# Sheet1.net
KiCad netlist of a schematic drawn in Altium Designer
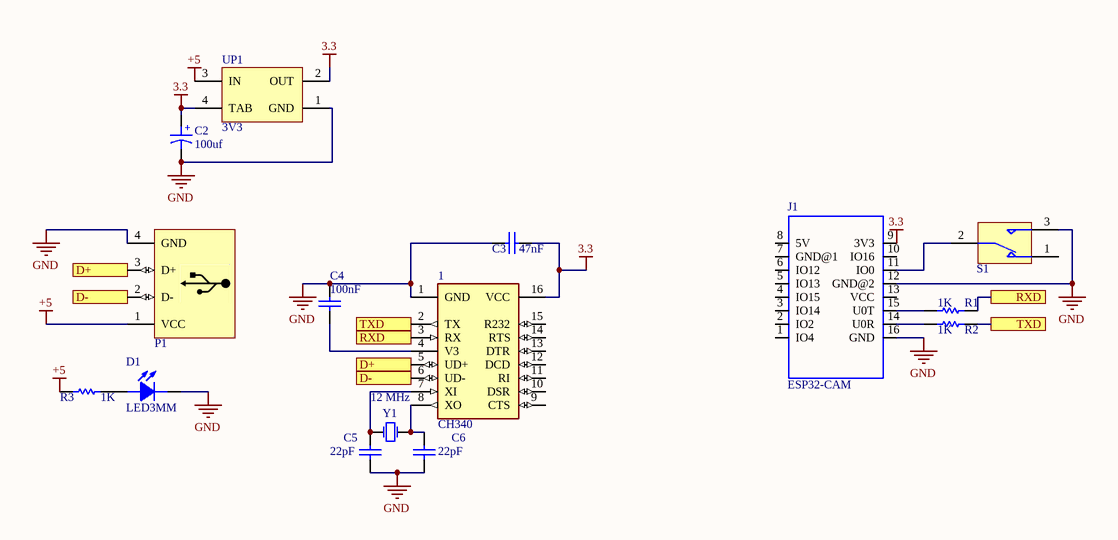
[diagram p0: Sheet1.SchDoc]

(export (version "E")
  (design (tool "Eeschema 10.0.6"))
  (components
    (comp (ref "1")
      (value "CH340")
      (footprint "SOIC16")
      (description "Circuit Breaker Magnetic 3Pole 40A 240VAC")
      (fields (field (name "MF") "Eaton"))
      (libsource (lib "CH340") (part "CH340"))
    )
    (comp (ref "C2")
      (value "100uf")
      (footprint "Cap electrolitic radial 6.3x12-2.5")
      (description "Cap electrolitic radial")
      (fields (field (name "DESIGNER") "Abbas Basereh"))
      (libsource (lib "Altium") (part "Cap ELECTROLITIC TOTAL SIZE"))
    )
    (comp (ref "C3")
      (value "47nF")
      (footprint "Cap-100nF")
      (description "CAP Ceramic Total")
      (fields (field (name "DESIGNER") "Ali Hafizi"))
      (libsource (lib "Altium") (part "CAP CERAMIC TOTAL SIZE"))
    )
    (comp (ref "C4")
      (value "100nF")
      (footprint "Cap-100nF")
      (description "CAP Ceramic Total")
      (fields (field (name "DESIGNER") "Ali Hafizi"))
      (libsource (lib "Altium") (part "CAP CERAMIC TOTAL SIZE"))
    )
    (comp (ref "C5")
      (value "22pF")
      (footprint "Cap-100nF")
      (description "CAP Ceramic Total")
      (fields (field (name "DESIGNER") "Ali Hafizi"))
      (libsource (lib "Altium") (part "CAP CERAMIC TOTAL SIZE"))
    )
    (comp (ref "C6")
      (value "22pF")
      (footprint "Cap-100nF")
      (description "CAP Ceramic Total")
      (fields (field (name "DESIGNER") "Ali Hafizi"))
      (libsource (lib "Altium") (part "CAP CERAMIC TOTAL SIZE"))
    )
    (comp (ref "D1")
      (value "LED3MM")
      (footprint "LED3mm_GRN")
      (description "Light Emitting Diode")
      (fields (field (name "DESIGNER") "Ali Hafizi"))
      (libsource (lib "Altium") (part "LED 3MM"))
    )
    (comp (ref "J1")
      (value "ESP32-CAM")
      (footprint "ESP32-CAM")
      (description "The smallest 802.11b/g/n Wi-Fi BT SoC Module")
      (fields (field (name "MF") "AI-Thinker"))
      (libsource (lib "ESP32-CAM") (part "ESP32-CAM"))
    )
    (comp (ref "P1")
      (value "USB Connector")
      (footprint "USB A TYPE Right Angle")
      (description "USB Connector-A Type")
      (libsource (lib "Altium") (part "USB A-Type"))
    )
    (comp (ref "R1")
      (value "1K")
      (footprint "RES-(1/4)")
      (description "TOTAL DIP RESISTOR PACK")
      (fields (field (name "DESIGNER") "Ali Hafizi"))
      (libsource (lib "Altium") (part "RES DIP PACKAGE"))
    )
    (comp (ref "R2")
      (value "1K")
      (footprint "RES-(1/4)")
      (description "TOTAL DIP RESISTOR PACK")
      (fields (field (name "DESIGNER") "Ali Hafizi"))
      (libsource (lib "Altium") (part "RES DIP PACKAGE"))
    )
    (comp (ref "R3")
      (value "1K")
      (footprint "RES-(1/4)")
      (description "TOTAL DIP RESISTOR PACK")
      (fields (field (name "DESIGNER") "Ali Hafizi"))
      (libsource (lib "Altium") (part "RES DIP PACKAGE"))
    )
    (comp (ref "S1")
      (value "Switch SPDT_Subminiator")
      (footprint "SPDT Subminiator")
      (description "Subminiator SPDT Switch")
      (libsource (lib "Altium") (part "Switch SPDT_Subminiator"))
    )
    (comp (ref "UP1")
      (value "3V3")
      (footprint "SOT223")
      (description "x.x Volt, 800mA Low-Dropout Linear Regulator, 4-pin SOT-223")
      (fields (field (name "DESIGNER") "Ali Hafizi"))
      (libsource (lib "Altium") (part "AMS1117-x.x"))
    )
    (comp (ref "Y1")
      (value "12 MHz")
      (footprint "XTAL 16MHZ")
      (description "XTAL Crystal")
      (fields (field (name "DESIGNER") "ABBAS BASEREH"))
      (libsource (lib "Altium") (part "XTAL"))
    )
  )
  (nets
    (net (code "1") (name "+5") (class "Default")
      (node (ref "P1") (pin "1") (pinfunction "VCC_1") (pintype "power_in"))
      (node (ref "R3") (pin "1") (pinfunction "1_1") (pintype "passive"))
      (node (ref "UP1") (pin "3") (pinfunction "IN_3") (pintype "power_in"))
    )
    (net (code "2") (name "/D+") (class "Default")
      (node (ref "1") (pin "5") (pinfunction "UD+_5") (pintype "bidirectional"))
      (node (ref "P1") (pin "3") (pinfunction "D+_3") (pintype "bidirectional"))
    )
    (net (code "3") (name "/D-") (class "Default")
      (node (ref "1") (pin "6") (pinfunction "UD-_6") (pintype "bidirectional"))
      (node (ref "P1") (pin "2") (pinfunction "D-_2") (pintype "bidirectional"))
    )
    (net (code "4") (name "/RXD") (class "Default")
      (node (ref "1") (pin "3") (pinfunction "RX_3") (pintype "input"))
      (node (ref "R1") (pin "1") (pinfunction "1_1") (pintype "passive"))
    )
    (net (code "5") (name "/TXD") (class "Default")
      (node (ref "1") (pin "2") (pinfunction "TX_2") (pintype "output"))
      (node (ref "R2") (pin "1") (pinfunction "1_1") (pintype "passive"))
    )
    (net (code "6") (name "3.3") (class "Default")
      (node (ref "1") (pin "16") (pinfunction "VCC_16") (pintype "power_in"))
      (node (ref "C2") (pin "1") (pinfunction "1_1") (pintype "passive"))
      (node (ref "C3") (pin "1") (pinfunction "1_1") (pintype "passive"))
      (node (ref "J1") (pin "9") (pinfunction "3V3_9") (pintype "power_in"))
      (node (ref "UP1") (pin "2") (pinfunction "OUT_2") (pintype "power_in"))
      (node (ref "UP1") (pin "4") (pinfunction "TAB_4") (pintype "power_in"))
    )
    (net (code "7") (name "GND") (class "Default")
      (node (ref "1") (pin "1") (pinfunction "GND_1") (pintype "power_in"))
      (node (ref "C2") (pin "2") (pinfunction "2_2") (pintype "passive"))
      (node (ref "C3") (pin "2") (pinfunction "2_2") (pintype "passive"))
      (node (ref "C4") (pin "2") (pinfunction "2_2") (pintype "passive"))
      (node (ref "C5") (pin "1") (pinfunction "1_1") (pintype "passive"))
      (node (ref "C6") (pin "1") (pinfunction "1_1") (pintype "passive"))
      (node (ref "D1") (pin "2") (pinfunction "CATHODE_2") (pintype "passive"))
      (node (ref "J1") (pin "12") (pinfunction "GND@2_12") (pintype "power_in"))
      (node (ref "J1") (pin "16") (pinfunction "GND_16") (pintype "power_in"))
      (node (ref "P1") (pin "4") (pinfunction "GND_4") (pintype "power_in"))
      (node (ref "S1") (pin "3") (pinfunction "3_3") (pintype "passive"))
      (node (ref "UP1") (pin "1") (pinfunction "GND_1") (pintype "power_in"))
    )
    (net (code "8") (name "Net-(1-V3)") (class "Default")
      (node (ref "1") (pin "4") (pinfunction "V3_4") (pintype "power_in"))
      (node (ref "C4") (pin "1") (pinfunction "1_1") (pintype "passive"))
    )
    (net (code "9") (name "Net-(1-XI)") (class "Default")
      (node (ref "1") (pin "7") (pinfunction "XI_7") (pintype "input"))
      (node (ref "C5") (pin "2") (pinfunction "2_2") (pintype "passive"))
      (node (ref "Y1") (pin "1") (pinfunction "OSC1_1") (pintype "passive"))
    )
    (net (code "10") (name "Net-(1-XO)") (class "Default")
      (node (ref "1") (pin "8") (pinfunction "XO_8") (pintype "output"))
      (node (ref "C6") (pin "2") (pinfunction "2_2") (pintype "passive"))
      (node (ref "Y1") (pin "2") (pinfunction "OSC2_2") (pintype "passive"))
    )
    (net (code "11") (name "Net-(D1-ANODE)") (class "Default")
      (node (ref "D1") (pin "1") (pinfunction "ANODE_1") (pintype "passive"))
      (node (ref "R3") (pin "2") (pinfunction "2_2") (pintype "passive"))
    )
    (net (code "12") (name "Net-(J1-IO0)") (class "Default")
      (node (ref "J1") (pin "11") (pinfunction "IO0_11") (pintype "bidirectional"))
      (node (ref "S1") (pin "2") (pinfunction "2_2") (pintype "passive"))
    )
    (net (code "13") (name "Net-(J1-U0R)") (class "Default")
      (node (ref "J1") (pin "14") (pinfunction "U0R_14") (pintype "power_in"))
      (node (ref "R2") (pin "2") (pinfunction "2_2") (pintype "passive"))
    )
    (net (code "14") (name "Net-(J1-U0T)") (class "Default")
      (node (ref "J1") (pin "15") (pinfunction "U0T_15") (pintype "bidirectional"))
      (node (ref "R1") (pin "2") (pinfunction "2_2") (pintype "passive"))
    )
    (net (code "15") (name "unconnected-(1-CTS-Pad9)") (class "Default")
      (node (ref "1") (pin "9") (pinfunction "CTS_9") (pintype "bidirectional"))
    )
    (net (code "16") (name "unconnected-(1-DCD-Pad12)") (class "Default")
      (node (ref "1") (pin "12") (pinfunction "DCD_12") (pintype "bidirectional"))
    )
    (net (code "17") (name "unconnected-(1-DSR-Pad10)") (class "Default")
      (node (ref "1") (pin "10") (pinfunction "DSR_10") (pintype "bidirectional"))
    )
    (net (code "18") (name "unconnected-(1-DTR-Pad13)") (class "Default")
      (node (ref "1") (pin "13") (pinfunction "DTR_13") (pintype "bidirectional"))
    )
    (net (code "19") (name "unconnected-(1-R232-Pad15)") (class "Default")
      (node (ref "1") (pin "15") (pinfunction "R232_15") (pintype "bidirectional"))
    )
    (net (code "20") (name "unconnected-(1-RI-Pad11)") (class "Default")
      (node (ref "1") (pin "11") (pinfunction "RI_11") (pintype "bidirectional"))
    )
    (net (code "21") (name "unconnected-(1-RTS-Pad14)") (class "Default")
      (node (ref "1") (pin "14") (pinfunction "RTS_14") (pintype "bidirectional"))
    )
    (net (code "22") (name "unconnected-(J1-5V-Pad8)") (class "Default")
      (node (ref "J1") (pin "8") (pinfunction "5V_8") (pintype "power_in"))
    )
    (net (code "23") (name "unconnected-(J1-GND@1-Pad7)") (class "Default")
      (node (ref "J1") (pin "7") (pinfunction "GND@1_7") (pintype "power_in"))
    )
    (net (code "24") (name "unconnected-(J1-IO2-Pad2)") (class "Default")
      (node (ref "J1") (pin "2") (pinfunction "IO2_2") (pintype "bidirectional"))
    )
    (net (code "25") (name "unconnected-(J1-IO4-Pad1)") (class "Default")
      (node (ref "J1") (pin "1") (pinfunction "IO4_1") (pintype "bidirectional"))
    )
    (net (code "26") (name "unconnected-(J1-IO12-Pad6)") (class "Default")
      (node (ref "J1") (pin "6") (pinfunction "IO12_6") (pintype "bidirectional"))
    )
    (net (code "27") (name "unconnected-(J1-IO13-Pad5)") (class "Default")
      (node (ref "J1") (pin "5") (pinfunction "IO13_5") (pintype "bidirectional"))
    )
    (net (code "28") (name "unconnected-(J1-IO14-Pad3)") (class "Default")
      (node (ref "J1") (pin "3") (pinfunction "IO14_3") (pintype "bidirectional"))
    )
    (net (code "29") (name "unconnected-(J1-IO15-Pad4)") (class "Default")
      (node (ref "J1") (pin "4") (pinfunction "IO15_4") (pintype "bidirectional"))
    )
    (net (code "30") (name "unconnected-(J1-IO16-Pad10)") (class "Default")
      (node (ref "J1") (pin "10") (pinfunction "IO16_10") (pintype "bidirectional"))
    )
    (net (code "31") (name "unconnected-(J1-VCC-Pad13)") (class "Default")
      (node (ref "J1") (pin "13") (pinfunction "VCC_13") (pintype "power_in"))
    )
    (net (code "32") (name "unconnected-(S1-Pad1)") (class "Default")
      (node (ref "S1") (pin "1") (pinfunction "1_1") (pintype "passive"))
    )
  )
)
